# CONNECTORS.net
KiCad netlist of a schematic drawn in Altium Designer
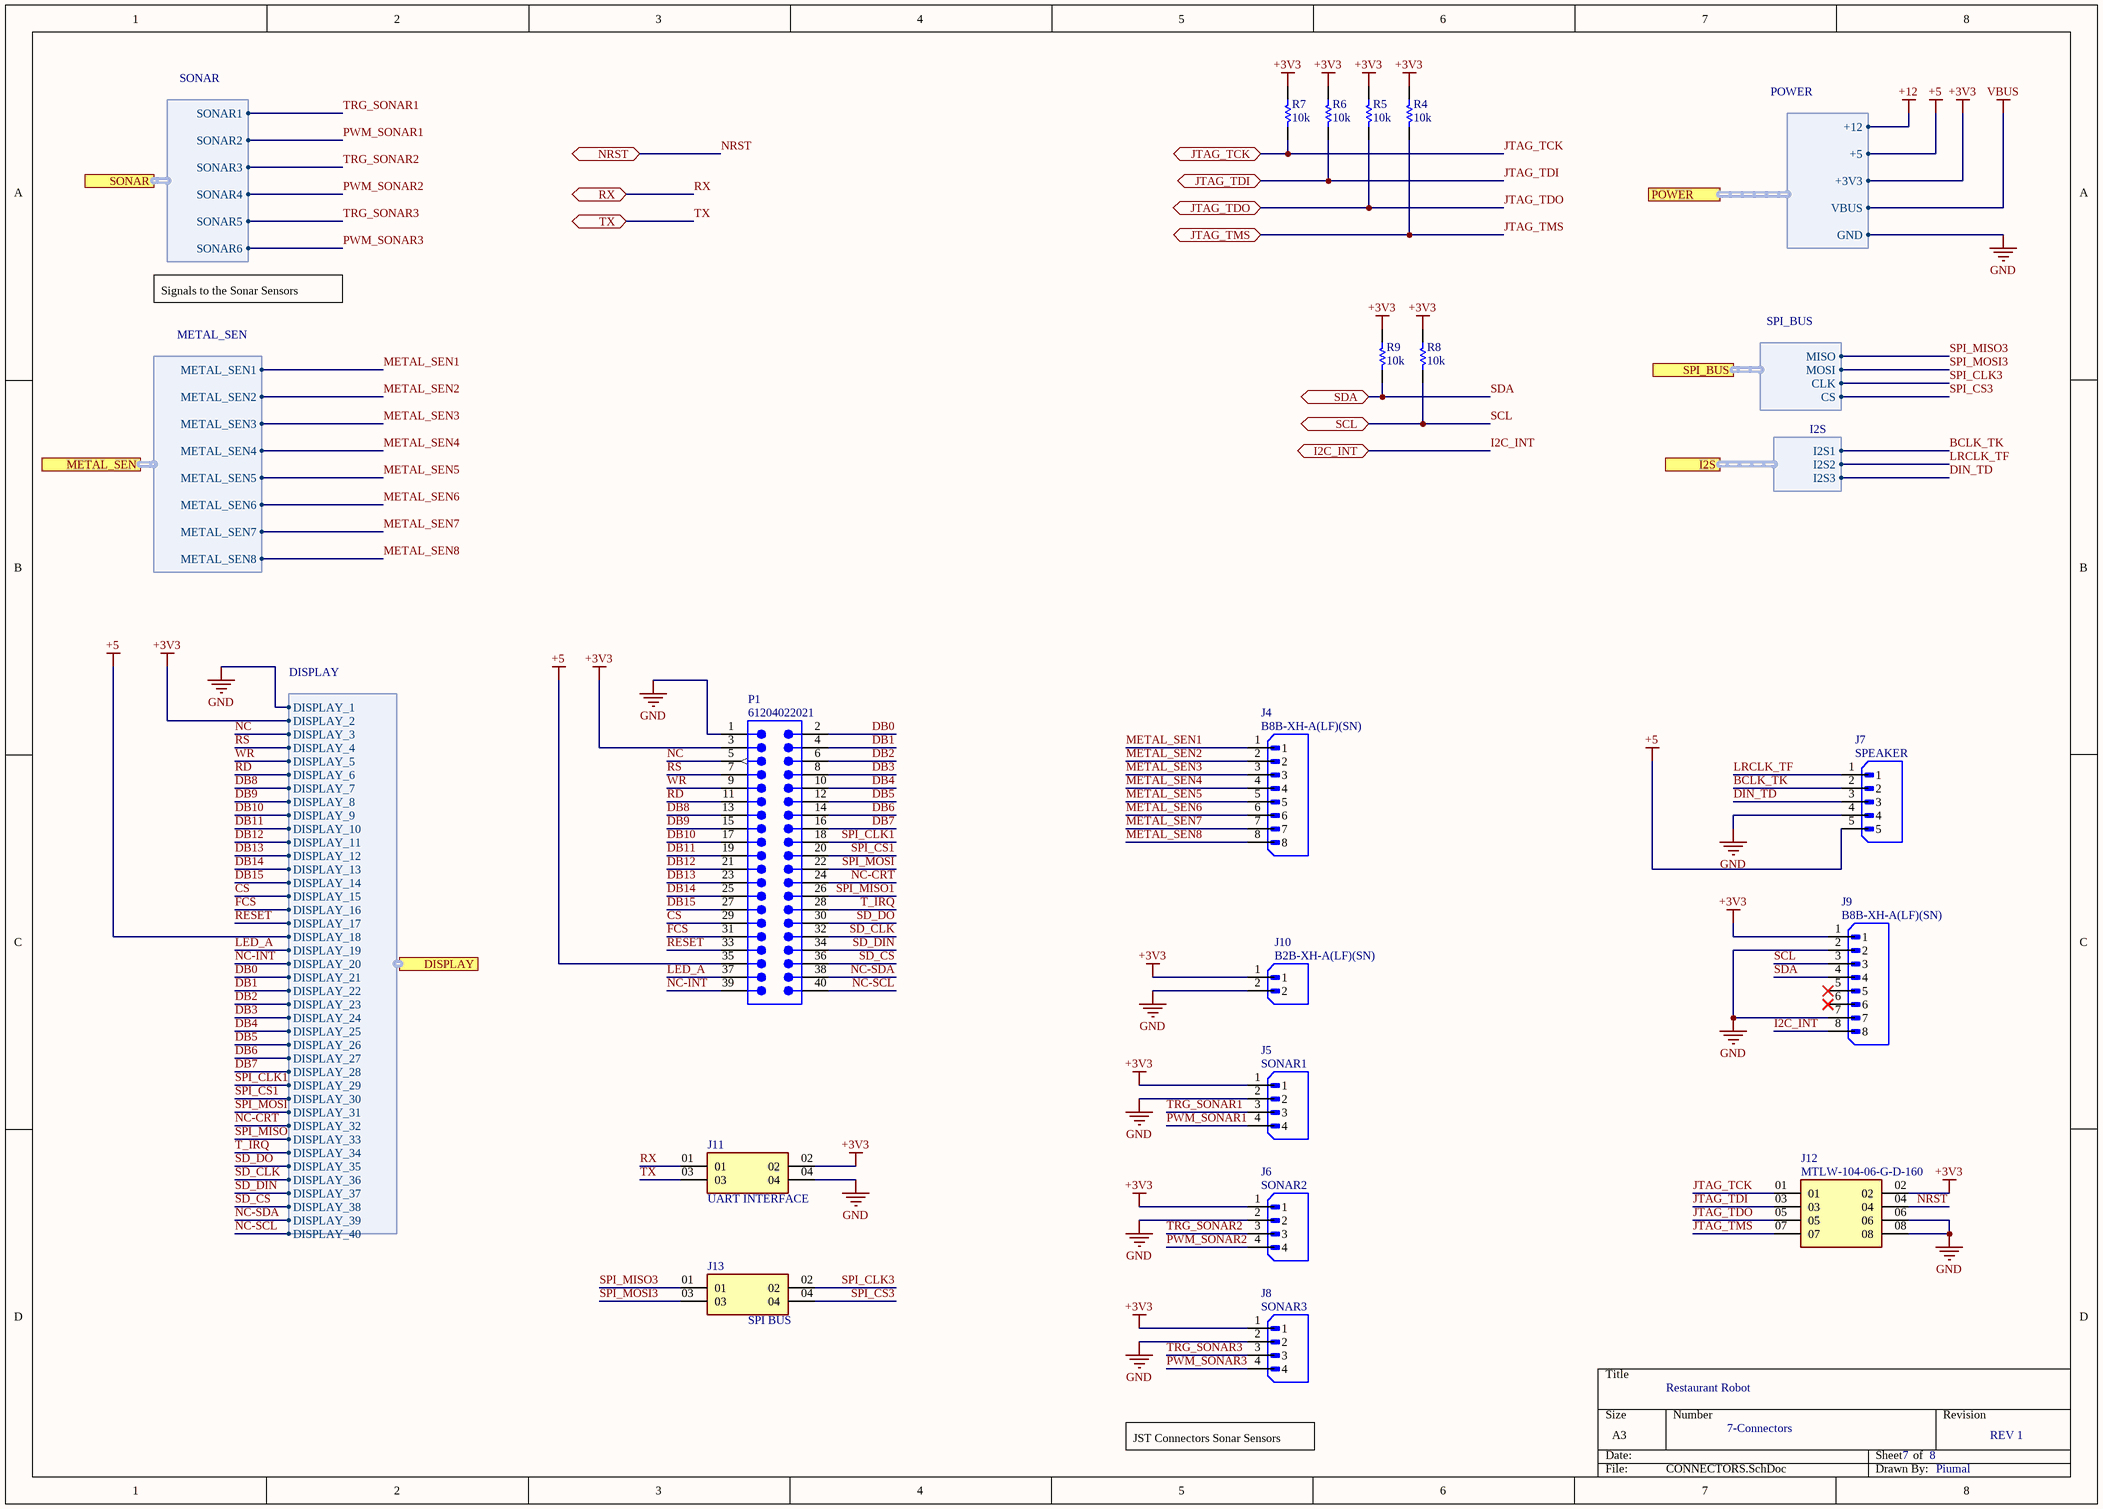
[diagram p0: CONNECTORS.SchDoc]

(export (version "E")
  (design (tool "Eeschema 10.0.6"))
  (components
    (comp (ref "J4")
      (value "B8B-XH-A(LF)(SN)")
      (footprint "JST_B8B-XH-A(LF)(SN)")
      (description "Connector Header Through Hole 8 position 0.098 (2.50mm)")
      (fields (field (name "MF") "JST Sales America Inc."))
      (libsource (lib "B8B-XH-A_LF__SN_ (1)") (part "B8B-XH-A(LF)(SN)"))
    )
    (comp (ref "J5")
      (value "SONAR1")
      (footprint "JST_B4B-XH-A(LF)(SN)")
      (description "Connector Header Through Hole 4 position 0.098 (2.50mm)")
      (fields (field (name "MF") "JST Sales") (field (name "MP") "B4B-XH-A(LF)(SN)"))
      (libsource (lib "B4B-XH-A_LF__SN_") (part "B4B-XH-A(LF)(SN)"))
    )
    (comp (ref "J6")
      (value "SONAR2")
      (footprint "JST_B4B-XH-A(LF)(SN)")
      (description "Connector Header Through Hole 4 position 0.098 (2.50mm)")
      (fields (field (name "MF") "JST Sales") (field (name "MP") "B4B-XH-A(LF)(SN)"))
      (libsource (lib "B4B-XH-A_LF__SN_") (part "B4B-XH-A(LF)(SN)"))
    )
    (comp (ref "J7")
      (value "SPEAKER")
      (footprint "JST_B5B-XH-A(LF)(SN)")
      (description "Connector Header Through Hole 5 position 0.098 (2.50mm)")
      (fields (field (name "MF") "JST Sales America Inc.") (field (name "MP") "B5B-XH-A(LF)(SN)"))
      (libsource (lib "B5B-XH-A_LF__SN_") (part "B5B-XH-A(LF)(SN)"))
    )
    (comp (ref "J8")
      (value "SONAR3")
      (footprint "JST_B4B-XH-A(LF)(SN)")
      (description "Connector Header Through Hole 4 position 0.098 (2.50mm)")
      (fields (field (name "MF") "JST Sales") (field (name "MP") "B4B-XH-A(LF)(SN)"))
      (libsource (lib "B4B-XH-A_LF__SN_") (part "B4B-XH-A(LF)(SN)"))
    )
    (comp (ref "J9")
      (value "B8B-XH-A(LF)(SN)")
      (footprint "JST_B8B-XH-A(LF)(SN)")
      (description "Connector Header Through Hole 8 position 0.098 (2.50mm)")
      (fields (field (name "MF") "JST Sales America Inc."))
      (libsource (lib "B8B-XH-A_LF__SN_ (1)") (part "B8B-XH-A(LF)(SN)"))
    )
    (comp (ref "J10")
      (value "B2B-XH-A(LF)(SN)")
      (footprint "JST_B2B-XH-A(LF)(SN)")
      (description "Connector Header Through Hole 2 position 0.098 (2.50mm)")
      (fields (field (name "MF") "JST Sales"))
      (libsource (lib "B2B-XH-A_LF__SN_") (part "B2B-XH-A(LF)(SN)"))
    )
    (comp (ref "J11")
      (value "UART INTERFACE")
      (footprint "SAMTEC_MTLW-102-XX-X-D-XXX")
      (description "Connector Header Through Hole 4 position 0.100 (2.54mm)")
      (fields (field (name "MF") "Samtec") (field (name "MP") "MTLW-102-05-G-D-180"))
      (libsource (lib "MTLW-102-XX-X-D-XXX") (part "MTLW-102-XX-X-D-XXX"))
    )
    (comp (ref "J12")
      (value "MTLW-104-06-G-D-160")
      (footprint "SAMTEC_MTLW-104-06-G-D-160")
      (libsource (lib "MTLW-104-06-G-D-160") (part "MTLW-104-06-G-D-160"))
    )
    (comp (ref "J13")
      (value "SPI BUS")
      (footprint "SAMTEC_MTLW-102-XX-X-D-XXX")
      (description "Connector Header Through Hole 4 position 0.100 (2.54mm)")
      (fields (field (name "MF") "Samtec") (field (name "MP") "MTLW-102-05-G-D-180"))
      (libsource (lib "MTLW-102-XX-X-D-XXX") (part "MTLW-102-XX-X-D-XXX"))
    )
    (comp (ref "P1")
      (value "61204022021")
      (footprint "61204022021")
      (libsource (lib "Altium Content Vault") (part "Header_Male_2R_40P"))
    )
    (comp (ref "R4")
      (value "RC0805JR-0710KL")
      (footprint "RESC2013X60X35ML10T20")
      (description "Chip Resistor, 10 KOhm, +/- 5%, 0.125 W, -55 to 155 degC, 0805 (2012 Metric), RoHS, Tape and Reel")
      (fields (field (name "MANUFACTURER") "Yageo") (field (name "RESISTANCE") "10k"))
      (libsource (lib "Altium Content Vault") (part "RES-2"))
    )
    (comp (ref "R5")
      (value "RC0805JR-0710KL")
      (footprint "RESC2013X60X35ML10T20")
      (description "Chip Resistor, 10 KOhm, +/- 5%, 0.125 W, -55 to 155 degC, 0805 (2012 Metric), RoHS, Tape and Reel")
      (fields (field (name "MANUFACTURER") "Yageo") (field (name "RESISTANCE") "10k"))
      (libsource (lib "Altium Content Vault") (part "RES-2"))
    )
    (comp (ref "R6")
      (value "RC0805JR-0710KL")
      (footprint "RESC2013X60X35ML10T20")
      (description "Chip Resistor, 10 KOhm, +/- 5%, 0.125 W, -55 to 155 degC, 0805 (2012 Metric), RoHS, Tape and Reel")
      (fields (field (name "MANUFACTURER") "Yageo") (field (name "RESISTANCE") "10k"))
      (libsource (lib "Altium Content Vault") (part "RES-2"))
    )
    (comp (ref "R7")
      (value "RC0805JR-0710KL")
      (footprint "RESC2013X60X35ML10T20")
      (description "Chip Resistor, 10 KOhm, +/- 5%, 0.125 W, -55 to 155 degC, 0805 (2012 Metric), RoHS, Tape and Reel")
      (fields (field (name "MANUFACTURER") "Yageo") (field (name "RESISTANCE") "10k"))
      (libsource (lib "Altium Content Vault") (part "RES-2"))
    )
    (comp (ref "R8")
      (value "RC0805JR-0710KL")
      (footprint "RESC2013X60X35ML10T20")
      (description "Chip Resistor, 10 KOhm, +/- 5%, 0.125 W, -55 to 155 degC, 0805 (2012 Metric), RoHS, Tape and Reel")
      (fields (field (name "MANUFACTURER") "Yageo") (field (name "RESISTANCE") "10k"))
      (libsource (lib "Altium Content Vault") (part "RES-2"))
    )
    (comp (ref "R9")
      (value "RC0805JR-0710KL")
      (footprint "RESC2013X60X35ML10T20")
      (description "Chip Resistor, 10 KOhm, +/- 5%, 0.125 W, -55 to 155 degC, 0805 (2012 Metric), RoHS, Tape and Reel")
      (fields (field (name "MANUFACTURER") "Yageo") (field (name "RESISTANCE") "10k"))
      (libsource (lib "Altium Content Vault") (part "RES-2"))
    )
  )
  (nets
    (net (code "7") (name "+3V3") (class "Default")
      (node (ref "J10") (pin "1") (pinfunction "1_1") (pintype "passive"))
      (node (ref "J11") (pin "02") (pinfunction "02_02") (pintype "passive"))
      (node (ref "J12") (pin "02") (pinfunction "02_02") (pintype "passive"))
      (node (ref "J5") (pin "1") (pinfunction "1_1") (pintype "passive"))
      (node (ref "J6") (pin "1") (pinfunction "1_1") (pintype "passive"))
      (node (ref "J8") (pin "1") (pinfunction "1_1") (pintype "passive"))
      (node (ref "J9") (pin "1") (pinfunction "1_1") (pintype "passive"))
      (node (ref "P1") (pin "3") (pinfunction "3_3") (pintype "passive"))
      (node (ref "R4") (pin "2") (pinfunction "2_2") (pintype "passive"))
      (node (ref "R5") (pin "2") (pinfunction "2_2") (pintype "passive"))
      (node (ref "R6") (pin "2") (pinfunction "2_2") (pintype "passive"))
      (node (ref "R7") (pin "2") (pinfunction "2_2") (pintype "passive"))
      (node (ref "R8") (pin "2") (pinfunction "2_2") (pintype "passive"))
      (node (ref "R9") (pin "2") (pinfunction "2_2") (pintype "passive"))
    )
    (net (code "8") (name "+5") (class "Default")
      (node (ref "J7") (pin "5") (pinfunction "5_5") (pintype "passive"))
      (node (ref "P1") (pin "35") (pinfunction "35_35") (pintype "passive"))
    )
    (net (code "10") (name "/BCLK_TK") (class "Default")
      (node (ref "J7") (pin "2") (pinfunction "2_2") (pintype "passive"))
    )
    (net (code "11") (name "/CS") (class "Default")
      (node (ref "P1") (pin "29") (pinfunction "29_29") (pintype "passive"))
    )
    (net (code "12") (name "/DB0") (class "Default")
      (node (ref "P1") (pin "2") (pinfunction "2_2") (pintype "passive"))
    )
    (net (code "13") (name "/DB1") (class "Default")
      (node (ref "P1") (pin "4") (pinfunction "4_4") (pintype "passive"))
    )
    (net (code "14") (name "/DB2") (class "Default")
      (node (ref "P1") (pin "6") (pinfunction "6_6") (pintype "passive"))
    )
    (net (code "15") (name "/DB3") (class "Default")
      (node (ref "P1") (pin "8") (pinfunction "8_8") (pintype "passive"))
    )
    (net (code "16") (name "/DB4") (class "Default")
      (node (ref "P1") (pin "10") (pinfunction "10_10") (pintype "passive"))
    )
    (net (code "17") (name "/DB5") (class "Default")
      (node (ref "P1") (pin "12") (pinfunction "12_12") (pintype "passive"))
    )
    (net (code "18") (name "/DB6") (class "Default")
      (node (ref "P1") (pin "14") (pinfunction "14_14") (pintype "passive"))
    )
    (net (code "19") (name "/DB7") (class "Default")
      (node (ref "P1") (pin "16") (pinfunction "16_16") (pintype "passive"))
    )
    (net (code "20") (name "/DB8") (class "Default")
      (node (ref "P1") (pin "13") (pinfunction "13_13") (pintype "passive"))
    )
    (net (code "21") (name "/DB9") (class "Default")
      (node (ref "P1") (pin "15") (pinfunction "15_15") (pintype "passive"))
    )
    (net (code "22") (name "/DB10") (class "Default")
      (node (ref "P1") (pin "17") (pinfunction "17_17") (pintype "passive"))
    )
    (net (code "23") (name "/DB11") (class "Default")
      (node (ref "P1") (pin "19") (pinfunction "19_19") (pintype "passive"))
    )
    (net (code "24") (name "/DB12") (class "Default")
      (node (ref "P1") (pin "21") (pinfunction "21_21") (pintype "passive"))
    )
    (net (code "25") (name "/DB13") (class "Default")
      (node (ref "P1") (pin "23") (pinfunction "23_23") (pintype "passive"))
    )
    (net (code "26") (name "/DB14") (class "Default")
      (node (ref "P1") (pin "25") (pinfunction "25_25") (pintype "passive"))
    )
    (net (code "27") (name "/DB15") (class "Default")
      (node (ref "P1") (pin "27") (pinfunction "27_27") (pintype "passive"))
    )
    (net (code "28") (name "/DIN_TD") (class "Default")
      (node (ref "J7") (pin "3") (pinfunction "3_3") (pintype "passive"))
    )
    (net (code "29") (name "/FCS") (class "Default")
      (node (ref "P1") (pin "31") (pinfunction "31_31") (pintype "passive"))
    )
    (net (code "30") (name "/I2C_INT") (class "Default")
      (node (ref "J9") (pin "8") (pinfunction "8_8") (pintype "passive"))
    )
    (net (code "31") (name "/JTAG_TCK") (class "Default")
      (node (ref "J12") (pin "01") (pinfunction "01_01") (pintype "passive"))
      (node (ref "R7") (pin "1") (pinfunction "1_1") (pintype "passive"))
    )
    (net (code "32") (name "/JTAG_TDI") (class "Default")
      (node (ref "J12") (pin "03") (pinfunction "03_03") (pintype "passive"))
      (node (ref "R6") (pin "1") (pinfunction "1_1") (pintype "passive"))
    )
    (net (code "33") (name "/JTAG_TDO") (class "Default")
      (node (ref "J12") (pin "05") (pinfunction "05_05") (pintype "passive"))
      (node (ref "R5") (pin "1") (pinfunction "1_1") (pintype "passive"))
    )
    (net (code "34") (name "/JTAG_TMS") (class "Default")
      (node (ref "J12") (pin "07") (pinfunction "07_07") (pintype "passive"))
      (node (ref "R4") (pin "1") (pinfunction "1_1") (pintype "passive"))
    )
    (net (code "35") (name "/LED_A") (class "Default")
      (node (ref "P1") (pin "37") (pinfunction "37_37") (pintype "passive"))
    )
    (net (code "36") (name "/LRCLK_TF") (class "Default")
      (node (ref "J7") (pin "1") (pinfunction "1_1") (pintype "passive"))
    )
    (net (code "37") (name "/METAL_SEN1") (class "Default")
      (node (ref "J4") (pin "1") (pinfunction "1_1") (pintype "passive"))
    )
    (net (code "38") (name "/METAL_SEN2") (class "Default")
      (node (ref "J4") (pin "2") (pinfunction "2_2") (pintype "passive"))
    )
    (net (code "39") (name "/METAL_SEN3") (class "Default")
      (node (ref "J4") (pin "3") (pinfunction "3_3") (pintype "passive"))
    )
    (net (code "40") (name "/METAL_SEN4") (class "Default")
      (node (ref "J4") (pin "4") (pinfunction "4_4") (pintype "passive"))
    )
    (net (code "41") (name "/METAL_SEN5") (class "Default")
      (node (ref "J4") (pin "5") (pinfunction "5_5") (pintype "passive"))
    )
    (net (code "42") (name "/METAL_SEN6") (class "Default")
      (node (ref "J4") (pin "6") (pinfunction "6_6") (pintype "passive"))
    )
    (net (code "43") (name "/METAL_SEN7") (class "Default")
      (node (ref "J4") (pin "7") (pinfunction "7_7") (pintype "passive"))
    )
    (net (code "44") (name "/METAL_SEN8") (class "Default")
      (node (ref "J4") (pin "8") (pinfunction "8_8") (pintype "passive"))
    )
    (net (code "45") (name "/NC") (class "Default")
      (node (ref "P1") (pin "5") (pinfunction "5_5") (pintype "output"))
    )
    (net (code "46") (name "/NC-CRT") (class "Default")
      (node (ref "P1") (pin "24") (pinfunction "24_24") (pintype "passive"))
    )
    (net (code "47") (name "/NC-INT") (class "Default")
      (node (ref "P1") (pin "39") (pinfunction "39_39") (pintype "passive"))
    )
    (net (code "48") (name "/NC-SCL") (class "Default")
      (node (ref "P1") (pin "40") (pinfunction "40_40") (pintype "passive"))
    )
    (net (code "49") (name "/NC-SDA") (class "Default")
      (node (ref "P1") (pin "38") (pinfunction "38_38") (pintype "passive"))
    )
    (net (code "50") (name "/NRST") (class "Default")
      (node (ref "J12") (pin "04") (pinfunction "04_04") (pintype "passive"))
    )
    (net (code "51") (name "/PWM_SONAR1") (class "Default")
      (node (ref "J5") (pin "4") (pinfunction "4_4") (pintype "passive"))
    )
    (net (code "52") (name "/PWM_SONAR2") (class "Default")
      (node (ref "J6") (pin "4") (pinfunction "4_4") (pintype "passive"))
    )
    (net (code "53") (name "/PWM_SONAR3") (class "Default")
      (node (ref "J8") (pin "4") (pinfunction "4_4") (pintype "passive"))
    )
    (net (code "54") (name "/RD") (class "Default")
      (node (ref "P1") (pin "11") (pinfunction "11_11") (pintype "passive"))
    )
    (net (code "55") (name "/RESET") (class "Default")
      (node (ref "P1") (pin "33") (pinfunction "33_33") (pintype "passive"))
    )
    (net (code "56") (name "/RS") (class "Default")
      (node (ref "P1") (pin "7") (pinfunction "7_7") (pintype "passive"))
    )
    (net (code "57") (name "/RX") (class "Default")
      (node (ref "J11") (pin "01") (pinfunction "01_01") (pintype "passive"))
    )
    (net (code "58") (name "/SCL") (class "Default")
      (node (ref "J9") (pin "3") (pinfunction "3_3") (pintype "passive"))
      (node (ref "R8") (pin "1") (pinfunction "1_1") (pintype "passive"))
    )
    (net (code "59") (name "/SDA") (class "Default")
      (node (ref "J9") (pin "4") (pinfunction "4_4") (pintype "passive"))
      (node (ref "R9") (pin "1") (pinfunction "1_1") (pintype "passive"))
    )
    (net (code "60") (name "/SD_CLK") (class "Default")
      (node (ref "P1") (pin "32") (pinfunction "32_32") (pintype "passive"))
    )
    (net (code "61") (name "/SD_CS") (class "Default")
      (node (ref "P1") (pin "36") (pinfunction "36_36") (pintype "passive"))
    )
    (net (code "62") (name "/SD_DIN") (class "Default")
      (node (ref "P1") (pin "34") (pinfunction "34_34") (pintype "passive"))
    )
    (net (code "63") (name "/SD_DO") (class "Default")
      (node (ref "P1") (pin "30") (pinfunction "30_30") (pintype "passive"))
    )
    (net (code "64") (name "/SPI_CLK1") (class "Default")
      (node (ref "P1") (pin "18") (pinfunction "18_18") (pintype "passive"))
    )
    (net (code "65") (name "/SPI_CLK3") (class "Default")
      (node (ref "J13") (pin "02") (pinfunction "02_02") (pintype "passive"))
    )
    (net (code "66") (name "/SPI_CS1") (class "Default")
      (node (ref "P1") (pin "20") (pinfunction "20_20") (pintype "passive"))
    )
    (net (code "67") (name "/SPI_CS3") (class "Default")
      (node (ref "J13") (pin "04") (pinfunction "04_04") (pintype "passive"))
    )
    (net (code "68") (name "/SPI_MISO1") (class "Default")
      (node (ref "P1") (pin "26") (pinfunction "26_26") (pintype "passive"))
    )
    (net (code "69") (name "/SPI_MISO3") (class "Default")
      (node (ref "J13") (pin "01") (pinfunction "01_01") (pintype "passive"))
    )
    (net (code "70") (name "/SPI_MOSI") (class "Default")
      (node (ref "P1") (pin "22") (pinfunction "22_22") (pintype "passive"))
    )
    (net (code "71") (name "/SPI_MOSI3") (class "Default")
      (node (ref "J13") (pin "03") (pinfunction "03_03") (pintype "passive"))
    )
    (net (code "72") (name "/TRG_SONAR1") (class "Default")
      (node (ref "J5") (pin "3") (pinfunction "3_3") (pintype "passive"))
    )
    (net (code "73") (name "/TRG_SONAR2") (class "Default")
      (node (ref "J6") (pin "3") (pinfunction "3_3") (pintype "passive"))
    )
    (net (code "74") (name "/TRG_SONAR3") (class "Default")
      (node (ref "J8") (pin "3") (pinfunction "3_3") (pintype "passive"))
    )
    (net (code "75") (name "/TX") (class "Default")
      (node (ref "J11") (pin "03") (pinfunction "03_03") (pintype "passive"))
    )
    (net (code "76") (name "/T_IRQ") (class "Default")
      (node (ref "P1") (pin "28") (pinfunction "28_28") (pintype "passive"))
    )
    (net (code "77") (name "/WR") (class "Default")
      (node (ref "P1") (pin "9") (pinfunction "9_9") (pintype "passive"))
    )
    (net (code "84") (name "GND") (class "Default")
      (node (ref "J10") (pin "2") (pinfunction "2_2") (pintype "passive"))
      (node (ref "J11") (pin "04") (pinfunction "04_04") (pintype "passive"))
      (node (ref "J12") (pin "06") (pinfunction "06_06") (pintype "passive"))
      (node (ref "J12") (pin "08") (pinfunction "08_08") (pintype "passive"))
      (node (ref "J5") (pin "2") (pinfunction "2_2") (pintype "passive"))
      (node (ref "J6") (pin "2") (pinfunction "2_2") (pintype "passive"))
      (node (ref "J7") (pin "4") (pinfunction "4_4") (pintype "passive"))
      (node (ref "J8") (pin "2") (pinfunction "2_2") (pintype "passive"))
      (node (ref "J9") (pin "2") (pinfunction "2_2") (pintype "passive"))
      (node (ref "J9") (pin "7") (pinfunction "7_7") (pintype "passive"))
      (node (ref "P1") (pin "1") (pinfunction "1_1") (pintype "passive"))
    )
    (net (code "86") (name "unconnected-(J9-Pad5)") (class "Default")
      (node (ref "J9") (pin "5") (pinfunction "5_5") (pintype "passive+no_connect"))
    )
    (net (code "87") (name "unconnected-(J9-Pad6)") (class "Default")
      (node (ref "J9") (pin "6") (pinfunction "6_6") (pintype "passive+no_connect"))
    )
  )
)
